# Sensor2.net
KiCad netlist of a schematic drawn in EAGLE
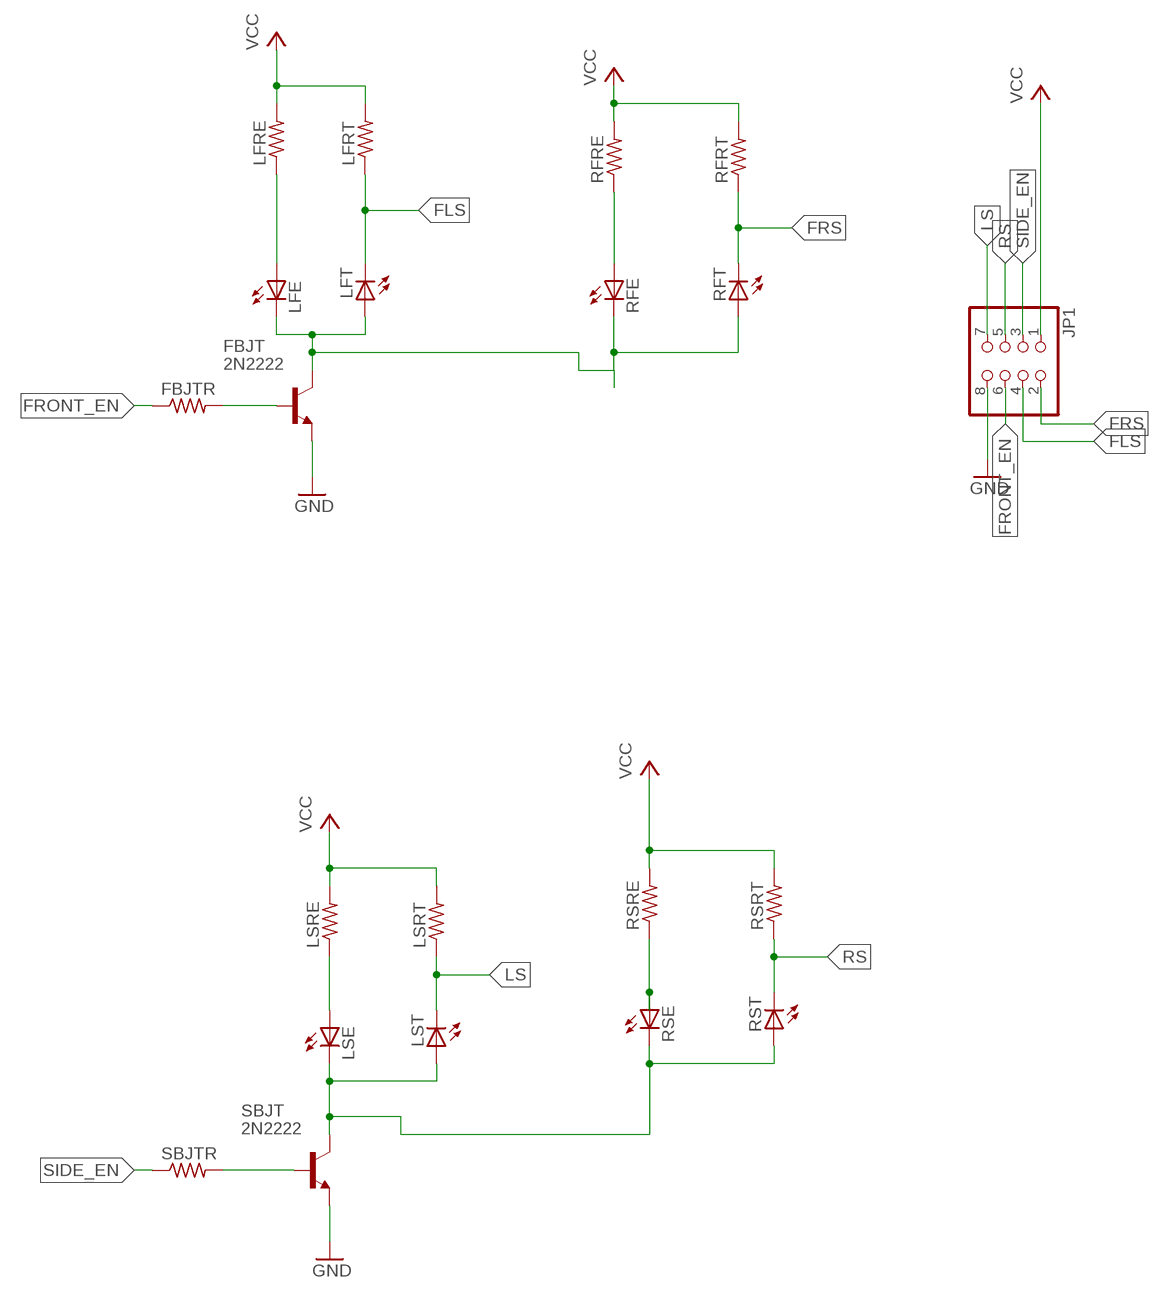
[diagram p0: schematic, sheet 1]

(export (version "E")
  (design (tool "Eeschema 10.0.6"))
  (components
    (comp (ref "FBJT")
      (value "2N2222")
      (footprint "eagle-import:TO92-EBC-OVAL")
      (libsource (lib "eagle-import") (part "2N2222"))
    )
    (comp (ref "FBJTR")
      (value "R-US_R0805")
      (footprint "eagle-import:R0805")
      (libsource (lib "eagle-import") (part "R-US_R0805"))
    )
    (comp (ref "JP1")
      (value "PINHD-2X4")
      (footprint "eagle-import:2X04")
      (libsource (lib "eagle-import") (part "PINHD-2X4"))
    )
    (comp (ref "LFE")
      (value "LED5MM")
      (footprint "eagle-import:LED5MM")
      (libsource (lib "eagle-import") (part "LED5MM"))
    )
    (comp (ref "LFRE")
      (value "R-US_R0805")
      (footprint "eagle-import:R0805")
      (libsource (lib "eagle-import") (part "R-US_R0805"))
    )
    (comp (ref "LFRT")
      (value "R-US_R0805")
      (footprint "eagle-import:R0805")
      (libsource (lib "eagle-import") (part "R-US_R0805"))
    )
    (comp (ref "LFT")
      (value "LED5MM")
      (footprint "eagle-import:LED5MM")
      (libsource (lib "eagle-import") (part "LED5MM"))
    )
    (comp (ref "LSE")
      (value "LED5MM")
      (footprint "eagle-import:LED5MM")
      (libsource (lib "eagle-import") (part "LED5MM"))
    )
    (comp (ref "LSRE")
      (value "R-US_R0805")
      (footprint "eagle-import:R0805")
      (libsource (lib "eagle-import") (part "R-US_R0805"))
    )
    (comp (ref "LSRT")
      (value "R-US_R0805")
      (footprint "eagle-import:R0805")
      (libsource (lib "eagle-import") (part "R-US_R0805"))
    )
    (comp (ref "LST")
      (value "LED5MM")
      (footprint "eagle-import:LED5MM")
      (libsource (lib "eagle-import") (part "LED5MM"))
    )
    (comp (ref "RFE")
      (value "LED5MM")
      (footprint "eagle-import:LED5MM")
      (libsource (lib "eagle-import") (part "LED5MM"))
    )
    (comp (ref "RFRE")
      (value "R-US_R0805")
      (footprint "eagle-import:R0805")
      (libsource (lib "eagle-import") (part "R-US_R0805"))
    )
    (comp (ref "RFRT")
      (value "R-US_R0805")
      (footprint "eagle-import:R0805")
      (libsource (lib "eagle-import") (part "R-US_R0805"))
    )
    (comp (ref "RFT")
      (value "LED5MM")
      (footprint "eagle-import:LED5MM")
      (libsource (lib "eagle-import") (part "LED5MM"))
    )
    (comp (ref "RSE")
      (value "LED5MM")
      (footprint "eagle-import:LED5MM")
      (libsource (lib "eagle-import") (part "LED5MM"))
    )
    (comp (ref "RSRE")
      (value "R-US_R0805")
      (footprint "eagle-import:R0805")
      (libsource (lib "eagle-import") (part "R-US_R0805"))
    )
    (comp (ref "RSRT")
      (value "R-US_R0805")
      (footprint "eagle-import:R0805")
      (libsource (lib "eagle-import") (part "R-US_R0805"))
    )
    (comp (ref "RST")
      (value "LED5MM")
      (footprint "eagle-import:LED5MM")
      (libsource (lib "eagle-import") (part "LED5MM"))
    )
    (comp (ref "SBJT")
      (value "2N2222")
      (footprint "eagle-import:TO92-EBC-OVAL")
      (libsource (lib "eagle-import") (part "2N2222"))
    )
    (comp (ref "SBJTR")
      (value "R-US_R0805")
      (footprint "eagle-import:R0805")
      (libsource (lib "eagle-import") (part "R-US_R0805"))
    )
  )
  (nets
    (net (code "1") (name "FLS") (class "Default")
      (node (ref "JP1") (pin "4") (pinfunction "4_4") (pintype "passive"))
      (node (ref "LFRT") (pin "1") (pinfunction "1_1") (pintype "passive"))
      (node (ref "LFT") (pin "K") (pinfunction "C_K") (pintype "passive"))
    )
    (net (code "2") (name "FRONT_EN") (class "Default")
      (node (ref "FBJTR") (pin "1") (pinfunction "1_1") (pintype "passive"))
      (node (ref "JP1") (pin "6") (pinfunction "6_6") (pintype "passive"))
    )
    (net (code "3") (name "FRS") (class "Default")
      (node (ref "JP1") (pin "2") (pinfunction "2_2") (pintype "passive"))
      (node (ref "RFRT") (pin "1") (pinfunction "1_1") (pintype "passive"))
      (node (ref "RFT") (pin "K") (pinfunction "C_K") (pintype "passive"))
    )
    (net (code "4") (name "GND") (class "Default")
      (node (ref "FBJT") (pin "E") (pinfunction "E_E") (pintype "passive"))
      (node (ref "JP1") (pin "8") (pinfunction "8_8") (pintype "passive"))
      (node (ref "SBJT") (pin "E") (pinfunction "E_E") (pintype "passive"))
    )
    (net (code "5") (name "LS") (class "Default")
      (node (ref "JP1") (pin "7") (pinfunction "7_7") (pintype "passive"))
      (node (ref "LSRT") (pin "1") (pinfunction "1_1") (pintype "passive"))
      (node (ref "LST") (pin "K") (pinfunction "C_K") (pintype "passive"))
    )
    (net (code "6") (name "Net-(FBJT-PadB)") (class "Default")
      (node (ref "FBJT") (pin "B") (pinfunction "B_B") (pintype "passive"))
      (node (ref "FBJTR") (pin "2") (pinfunction "2_2") (pintype "passive"))
    )
    (net (code "7") (name "Net-(LFE-C)") (class "Default")
      (node (ref "FBJT") (pin "C") (pinfunction "C_C") (pintype "passive"))
      (node (ref "LFE") (pin "K") (pinfunction "C_K") (pintype "passive"))
      (node (ref "LFT") (pin "A") (pinfunction "A_A") (pintype "passive"))
      (node (ref "RFE") (pin "K") (pinfunction "C_K") (pintype "passive"))
      (node (ref "RFT") (pin "A") (pinfunction "A_A") (pintype "passive"))
    )
    (net (code "8") (name "Net-(LFE-PadA)") (class "Default")
      (node (ref "LFE") (pin "A") (pinfunction "A_A") (pintype "passive"))
      (node (ref "LFRE") (pin "1") (pinfunction "1_1") (pintype "passive"))
    )
    (net (code "9") (name "Net-(LSE-C)") (class "Default")
      (node (ref "LSE") (pin "K") (pinfunction "C_K") (pintype "passive"))
      (node (ref "LST") (pin "A") (pinfunction "A_A") (pintype "passive"))
      (node (ref "RSE") (pin "K") (pinfunction "C_K") (pintype "passive"))
      (node (ref "RST") (pin "A") (pinfunction "A_A") (pintype "passive"))
      (node (ref "SBJT") (pin "C") (pinfunction "C_C") (pintype "passive"))
    )
    (net (code "10") (name "Net-(LSE-PadA)") (class "Default")
      (node (ref "LSE") (pin "A") (pinfunction "A_A") (pintype "passive"))
      (node (ref "LSRE") (pin "1") (pinfunction "1_1") (pintype "passive"))
    )
    (net (code "11") (name "Net-(RFE-PadA)") (class "Default")
      (node (ref "RFE") (pin "A") (pinfunction "A_A") (pintype "passive"))
      (node (ref "RFRE") (pin "1") (pinfunction "1_1") (pintype "passive"))
    )
    (net (code "12") (name "Net-(RSE-PadA)") (class "Default")
      (node (ref "RSE") (pin "A") (pinfunction "A_A") (pintype "passive"))
      (node (ref "RSRE") (pin "1") (pinfunction "1_1") (pintype "passive"))
    )
    (net (code "13") (name "Net-(SBJT-PadB)") (class "Default")
      (node (ref "SBJT") (pin "B") (pinfunction "B_B") (pintype "passive"))
      (node (ref "SBJTR") (pin "2") (pinfunction "2_2") (pintype "passive"))
    )
    (net (code "14") (name "RS") (class "Default")
      (node (ref "JP1") (pin "5") (pinfunction "5_5") (pintype "passive"))
      (node (ref "RSRT") (pin "1") (pinfunction "1_1") (pintype "passive"))
      (node (ref "RST") (pin "K") (pinfunction "C_K") (pintype "passive"))
    )
    (net (code "15") (name "SIDE_EN") (class "Default")
      (node (ref "JP1") (pin "3") (pinfunction "3_3") (pintype "passive"))
      (node (ref "SBJTR") (pin "1") (pinfunction "1_1") (pintype "passive"))
    )
    (net (code "16") (name "VCC") (class "Default")
      (node (ref "JP1") (pin "1") (pinfunction "1_1") (pintype "passive"))
      (node (ref "LFRE") (pin "2") (pinfunction "2_2") (pintype "passive"))
      (node (ref "LFRT") (pin "2") (pinfunction "2_2") (pintype "passive"))
      (node (ref "LSRE") (pin "2") (pinfunction "2_2") (pintype "passive"))
      (node (ref "LSRT") (pin "2") (pinfunction "2_2") (pintype "passive"))
      (node (ref "RFRE") (pin "2") (pinfunction "2_2") (pintype "passive"))
      (node (ref "RFRT") (pin "2") (pinfunction "2_2") (pintype "passive"))
      (node (ref "RSRE") (pin "2") (pinfunction "2_2") (pintype "passive"))
      (node (ref "RSRT") (pin "2") (pinfunction "2_2") (pintype "passive"))
    )
  )
)
